# 03_Power_Spply.net
KiCad netlist of a schematic drawn in Altium Designer
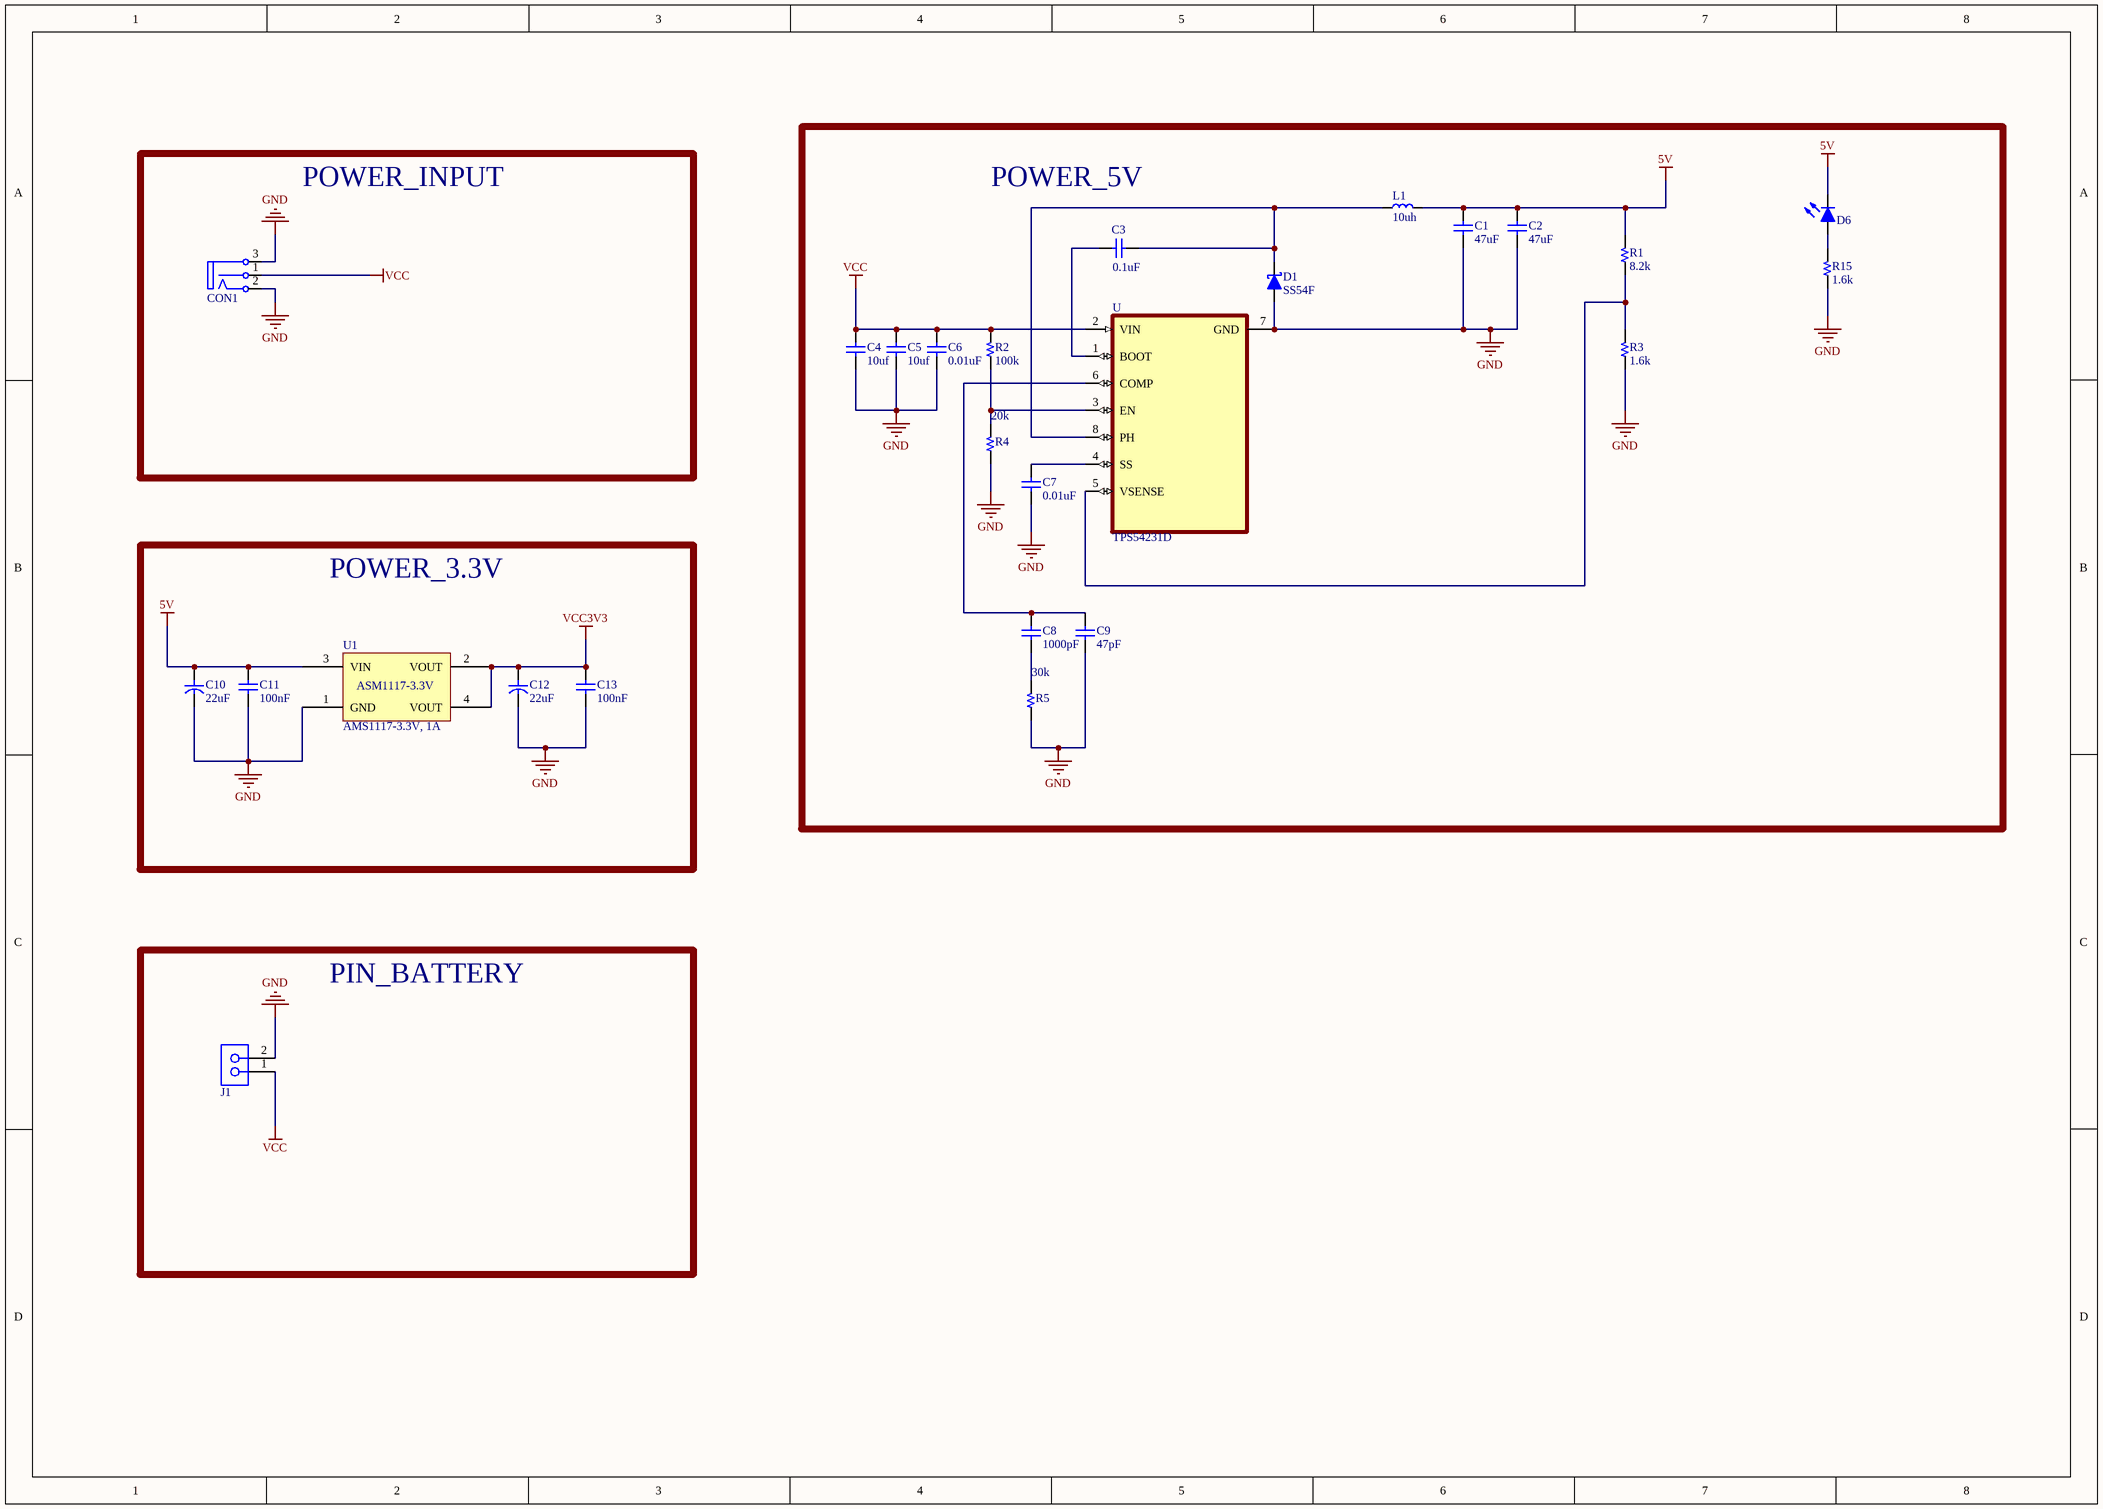
[diagram p0: 03_Power_Spply.SchDoc]

(export (version "E")
  (design (tool "Eeschema 10.0.6"))
  (components
    (comp (ref "C1")
      (value "47uF")
      (footprint "C 0805")
      (description "Capacitor non-pol")
      (libsource (lib "chipfc_libs") (part "Capacitor NP"))
    )
    (comp (ref "C2")
      (value "47uF")
      (footprint "C 0805")
      (description "Capacitor non-pol")
      (libsource (lib "chipfc_libs") (part "Capacitor NP"))
    )
    (comp (ref "C3")
      (value "0.1uF")
      (footprint "C 0805")
      (description "Capacitor non-pol")
      (libsource (lib "chipfc_libs") (part "Capacitor NP"))
    )
    (comp (ref "C4")
      (value "10uf")
      (footprint "C 0805")
      (description "Capacitor non-pol")
      (libsource (lib "chipfc_libs") (part "Capacitor NP"))
    )
    (comp (ref "C5")
      (value "10uf")
      (footprint "C 0805")
      (description "Capacitor non-pol")
      (libsource (lib "chipfc_libs") (part "Capacitor NP"))
    )
    (comp (ref "C6")
      (value "0.01uF")
      (footprint "C 0805")
      (description "Capacitor non-pol")
      (libsource (lib "chipfc_libs") (part "Capacitor NP"))
    )
    (comp (ref "C7")
      (value "0.01uF")
      (footprint "C 0805")
      (description "Capacitor non-pol")
      (libsource (lib "chipfc_libs") (part "Capacitor NP"))
    )
    (comp (ref "C8")
      (value "1000pF")
      (footprint "C 0805")
      (description "Capacitor non-pol")
      (libsource (lib "chipfc_libs") (part "Capacitor NP"))
    )
    (comp (ref "C9")
      (value "47pF")
      (footprint "C 0805")
      (description "Capacitor non-pol")
      (libsource (lib "chipfc_libs") (part "Capacitor NP"))
    )
    (comp (ref "C10")
      (value "22uF")
      (footprint "C SMD TAN 2312 (C)")
      (description "Capacitor pol")
      (libsource (lib "chipfc_libs") (part "Capacitor"))
    )
    (comp (ref "C11")
      (value "100nF")
      (footprint "C 0805")
      (description "Capacitor non-pol")
      (libsource (lib "chipfc_libs") (part "Capacitor NP"))
    )
    (comp (ref "C12")
      (value "22uF")
      (footprint "C SMD TAN 2312 (C)")
      (description "Capacitor pol")
      (libsource (lib "chipfc_libs") (part "Capacitor"))
    )
    (comp (ref "C13")
      (value "100nF")
      (footprint "C 0805")
      (description "Capacitor non-pol")
      (libsource (lib "chipfc_libs") (part "Capacitor NP"))
    )
    (comp (ref "CON1")
      (value "CON DC PWR")
      (footprint "CONN/DC/PWR/5.0MM")
      (description "DC input connector")
      (libsource (lib "connectors") (part "CON DC PWR"))
    )
    (comp (ref "D1")
      (value "SS54F")
      (footprint "DO-214AC (SMA)")
      (description "Schottky Diode")
      (libsource (lib "chipfc_libs") (part "Diode Schottky"))
    )
    (comp (ref "D6")
      (value "Led")
      (footprint "Led 0805")
      (description "Typical LED")
      (libsource (lib "led") (part "Led"))
    )
    (comp (ref "J1")
      (value "6A, 150V")
      (footprint "691402910002B")
      (description "WR-TBL Series 4029 Horizontal Entry, THT, pitch 2.54mm, 2p")
      (fields
        (field (name "MANUFACTURER PART NUMBER") "691402910002B")
        (field (name "MANUFACTURER") "Wurth Elektronik")
      )
      (libsource (lib "Terminal_Blocks_Spring_Clamp_2.54mm") (part "691402910002B"))
    )
    (comp (ref "L1")
      (value "10uh")
      (footprint "Inductor SMD CDRH3D67")
      (description "Inductor")
      (libsource (lib "chipfc_libs") (part "Inductor"))
    )
    (comp (ref "R1")
      (value "8.2k")
      (footprint "R 0805")
      (description "Resistor")
      (libsource (lib "chipfc_libs") (part "Resistor"))
    )
    (comp (ref "R2")
      (value "100k")
      (footprint "R 0805")
      (description "Resistor")
      (libsource (lib "chipfc_libs") (part "Resistor"))
    )
    (comp (ref "R3")
      (value "1.6k")
      (footprint "R 0805")
      (description "Resistor")
      (libsource (lib "chipfc_libs") (part "Resistor"))
    )
    (comp (ref "R4")
      (value "20k")
      (footprint "R 0805")
      (description "Resistor")
      (libsource (lib "chipfc_libs") (part "Resistor"))
    )
    (comp (ref "R5")
      (value "30k")
      (footprint "R 0805")
      (description "Resistor")
      (libsource (lib "chipfc_libs") (part "Resistor"))
    )
    (comp (ref "R15")
      (value "1.6k")
      (footprint "R 0805")
      (description "Resistor")
      (libsource (lib "chipfc_libs") (part "Resistor"))
    )
    (comp (ref "U")
      (value "TPS54231D")
      (footprint "SOIC127P599X175-8N")
      (description "å…·æœ‰Eco-modeï¼†tradeçš„3.5è‡³28Vè¾“å…¥ï¼Œ2Aï¼Œ570kHzé™åŽ‹è½¬æ¢å™¨ï¼›8-SOIC -40è‡³150")
      (fields (field (name "MF") "Texas Instruments"))
      (libsource (lib "TPS54231D") (part "TPS54231D"))
    )
    (comp (ref "U1")
      (value "AMS1117-3.3V, 1A")
      (footprint "AMS1117-3.3V SOT223")
      (description "1A 60dB@(120Hz) Fixed 3.3V Positive electrode 12V SOT-223 Linear Voltage Regulators (LDO) ROHS")
      (fields (field (name "MANUFACTURER") "AMS") (field (name "LCSC PART #") "C347222"))
      (libsource (lib "AMS_family") (part "AMS1117-3.3V"))
    )
  )
  (nets
    (net (code "1") (name "5V") (class "Default")
      (node (ref "C1") (pin "2") (pinfunction "2_2") (pintype "passive"))
      (node (ref "C10") (pin "1") (pinfunction "1_1") (pintype "passive"))
      (node (ref "C11") (pin "2") (pinfunction "2_2") (pintype "passive"))
      (node (ref "C2") (pin "2") (pinfunction "2_2") (pintype "passive"))
      (node (ref "D6") (pin "2") (pinfunction "K_2") (pintype "passive"))
      (node (ref "L1") (pin "2") (pinfunction "2_2") (pintype "passive"))
      (node (ref "R1") (pin "2") (pinfunction "2_2") (pintype "passive"))
      (node (ref "U1") (pin "3") (pinfunction "VIN_3") (pintype "passive"))
    )
    (net (code "2") (name "GND") (class "Default")
      (node (ref "C1") (pin "1") (pinfunction "1_1") (pintype "passive"))
      (node (ref "C10") (pin "2") (pinfunction "2_2") (pintype "passive"))
      (node (ref "C11") (pin "1") (pinfunction "1_1") (pintype "passive"))
      (node (ref "C12") (pin "2") (pinfunction "2_2") (pintype "passive"))
      (node (ref "C13") (pin "1") (pinfunction "1_1") (pintype "passive"))
      (node (ref "C2") (pin "1") (pinfunction "1_1") (pintype "passive"))
      (node (ref "C4") (pin "1") (pinfunction "1_1") (pintype "passive"))
      (node (ref "C5") (pin "1") (pinfunction "1_1") (pintype "passive"))
      (node (ref "C6") (pin "1") (pinfunction "1_1") (pintype "passive"))
      (node (ref "C7") (pin "1") (pinfunction "1_1") (pintype "passive"))
      (node (ref "C9") (pin "1") (pinfunction "1_1") (pintype "passive"))
      (node (ref "CON1") (pin "2") (pinfunction "T_2") (pintype "passive"))
      (node (ref "CON1") (pin "3") (pinfunction "TN_3") (pintype "passive"))
      (node (ref "D1") (pin "1") (pinfunction "A_1") (pintype "passive"))
      (node (ref "J1") (pin "2") (pinfunction "2_2") (pintype "passive"))
      (node (ref "R15") (pin "1") (pinfunction "1_1") (pintype "passive"))
      (node (ref "R3") (pin "1") (pinfunction "1_1") (pintype "passive"))
      (node (ref "R4") (pin "1") (pinfunction "1_1") (pintype "passive"))
      (node (ref "R5") (pin "1") (pinfunction "1_1") (pintype "passive"))
      (node (ref "U") (pin "7") (pinfunction "GND_7") (pintype "power_in"))
      (node (ref "U1") (pin "1") (pinfunction "GND_1") (pintype "power_in"))
    )
    (net (code "3") (name "Net-(C8-Pad1)") (class "Default")
      (node (ref "C8") (pin "1") (pinfunction "1_1") (pintype "passive"))
      (node (ref "R5") (pin "2") (pinfunction "2_2") (pintype "passive"))
    )
    (net (code "4") (name "Net-(D1-K)") (class "Default")
      (node (ref "C3") (pin "1") (pinfunction "1_1") (pintype "passive"))
      (node (ref "D1") (pin "2") (pinfunction "K_2") (pintype "passive"))
      (node (ref "L1") (pin "1") (pinfunction "1_1") (pintype "passive"))
      (node (ref "U") (pin "8") (pinfunction "PH_8") (pintype "bidirectional"))
    )
    (net (code "5") (name "Net-(D6-A)") (class "Default")
      (node (ref "D6") (pin "1") (pinfunction "A_1") (pintype "passive"))
      (node (ref "R15") (pin "2") (pinfunction "2_2") (pintype "passive"))
    )
    (net (code "6") (name "Net-(U-BOOT)") (class "Default")
      (node (ref "C3") (pin "2") (pinfunction "2_2") (pintype "passive"))
      (node (ref "U") (pin "1") (pinfunction "BOOT_1") (pintype "bidirectional"))
    )
    (net (code "7") (name "Net-(U-COMP)") (class "Default")
      (node (ref "C8") (pin "2") (pinfunction "2_2") (pintype "passive"))
      (node (ref "C9") (pin "2") (pinfunction "2_2") (pintype "passive"))
      (node (ref "U") (pin "6") (pinfunction "COMP_6") (pintype "bidirectional"))
    )
    (net (code "8") (name "Net-(U-EN)") (class "Default")
      (node (ref "R2") (pin "1") (pinfunction "1_1") (pintype "passive"))
      (node (ref "R4") (pin "2") (pinfunction "2_2") (pintype "passive"))
      (node (ref "U") (pin "3") (pinfunction "EN_3") (pintype "bidirectional"))
    )
    (net (code "9") (name "Net-(U-SS)") (class "Default")
      (node (ref "C7") (pin "2") (pinfunction "2_2") (pintype "passive"))
      (node (ref "U") (pin "4") (pinfunction "SS_4") (pintype "bidirectional"))
    )
    (net (code "10") (name "Net-(U-VSENSE)") (class "Default")
      (node (ref "R1") (pin "1") (pinfunction "1_1") (pintype "passive"))
      (node (ref "R3") (pin "2") (pinfunction "2_2") (pintype "passive"))
      (node (ref "U") (pin "5") (pinfunction "VSENSE_5") (pintype "bidirectional"))
    )
    (net (code "11") (name "VCC") (class "Default")
      (node (ref "C4") (pin "2") (pinfunction "2_2") (pintype "passive"))
      (node (ref "C5") (pin "2") (pinfunction "2_2") (pintype "passive"))
      (node (ref "C6") (pin "2") (pinfunction "2_2") (pintype "passive"))
      (node (ref "CON1") (pin "1") (pinfunction "S_1") (pintype "power_in"))
      (node (ref "J1") (pin "1") (pinfunction "1_1") (pintype "passive"))
      (node (ref "R2") (pin "2") (pinfunction "2_2") (pintype "passive"))
      (node (ref "U") (pin "2") (pinfunction "VIN_2") (pintype "input"))
    )
    (net (code "12") (name "VCC3V3") (class "Default")
      (node (ref "C12") (pin "1") (pinfunction "1_1") (pintype "passive"))
      (node (ref "C13") (pin "2") (pinfunction "2_2") (pintype "passive"))
      (node (ref "U1") (pin "2") (pinfunction "VOUT_2") (pintype "passive"))
      (node (ref "U1") (pin "4") (pinfunction "VOUT_4") (pintype "power_in"))
    )
  )
)
